# odd_v1.net
KiCad netlist of a schematic drawn in EAGLE
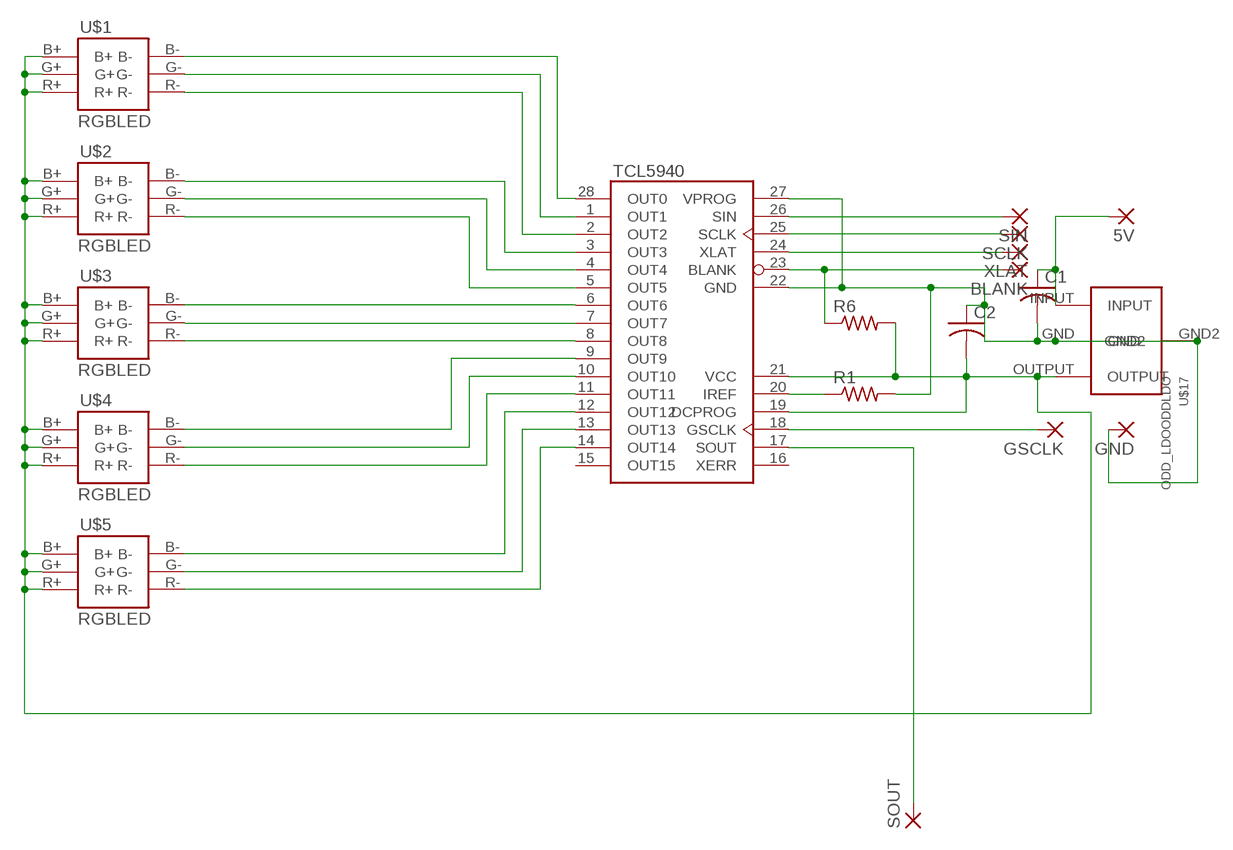
[diagram p0: schematic, sheet 1]

(export (version "E")
  (design (tool "Eeschema 10.0.6"))
  (components
    (comp (ref "5V")
      (value "2,54/1,1")
      (footprint "eagle-import:2,54_1,1")
      (libsource (lib "eagle-import") (part "2,54/1,1"))
    )
    (comp (ref "BLANK")
      (value "2,54/1,1")
      (footprint "eagle-import:2,54_1,1")
      (libsource (lib "eagle-import") (part "2,54/1,1"))
    )
    (comp (ref "C1")
      (value "C-US075-032X103")
      (footprint "eagle-import:C075-032X103")
      (libsource (lib "eagle-import") (part "C-US075-032X103"))
    )
    (comp (ref "C2")
      (value "C-US075-032X103")
      (footprint "eagle-import:C075-032X103")
      (libsource (lib "eagle-import") (part "C-US075-032X103"))
    )
    (comp (ref "GND")
      (value "2,54/1,1")
      (footprint "eagle-import:2,54_1,1")
      (libsource (lib "eagle-import") (part "2,54/1,1"))
    )
    (comp (ref "GSCLK")
      (value "2,54/1,1")
      (footprint "eagle-import:2,54_1,1")
      (libsource (lib "eagle-import") (part "2,54/1,1"))
    )
    (comp (ref "IC1")
      (value "TCL5940")
      (footprint "eagle-import:DIP28")
      (libsource (lib "eagle-import") (part "TCL5940"))
    )
    (comp (ref "R1")
      (value "R-US_0204/7")
      (footprint "eagle-import:0204_7")
      (libsource (lib "eagle-import") (part "R-US_0204/7"))
    )
    (comp (ref "R6")
      (value "R-US_0204/7")
      (footprint "eagle-import:0204_7")
      (libsource (lib "eagle-import") (part "R-US_0204/7"))
    )
    (comp (ref "SCLK")
      (value "2,54/1,1")
      (footprint "eagle-import:2,54_1,1")
      (libsource (lib "eagle-import") (part "2,54/1,1"))
    )
    (comp (ref "SIN")
      (value "2,54/1,1")
      (footprint "eagle-import:2,54_1,1")
      (libsource (lib "eagle-import") (part "2,54/1,1"))
    )
    (comp (ref "SOUT")
      (value "2,54/1,1")
      (footprint "eagle-import:2,54_1,1")
      (libsource (lib "eagle-import") (part "2,54/1,1"))
    )
    (comp (ref "U$1")
      (value "RGBLED")
      (footprint "eagle-import:6PADSMD")
      (libsource (lib "eagle-import") (part "CREESMDRGBLED6PADSMD"))
    )
    (comp (ref "U$2")
      (value "RGBLED")
      (footprint "eagle-import:6PADSMD")
      (libsource (lib "eagle-import") (part "CREESMDRGBLED6PADSMD"))
    )
    (comp (ref "U$3")
      (value "RGBLED")
      (footprint "eagle-import:6PADSMD")
      (libsource (lib "eagle-import") (part "CREESMDRGBLED6PADSMD"))
    )
    (comp (ref "U$4")
      (value "RGBLED")
      (footprint "eagle-import:6PADSMD")
      (libsource (lib "eagle-import") (part "CREESMDRGBLED6PADSMD"))
    )
    (comp (ref "U$5")
      (value "RGBLED")
      (footprint "eagle-import:6PADSMD")
      (libsource (lib "eagle-import") (part "CREESMDRGBLED6PADSMD"))
    )
    (comp (ref "U$17")
      (value "ODD_LDOODDLDO")
      (footprint "eagle-import:4PINLDO")
      (libsource (lib "eagle-import") (part "ODD_LDOODDLDO"))
    )
    (comp (ref "XLAT")
      (value "2,54/1,1")
      (footprint "eagle-import:2,54_1,1")
      (libsource (lib "eagle-import") (part "2,54/1,1"))
    )
  )
  (nets
    (net (code "1") (name "Net-(5V-P)") (class "Default")
      (node (ref "5V") (pin "1") (pinfunction "P_1") (pintype "passive"))
      (node (ref "C1") (pin "1") (pinfunction "1_1") (pintype "passive"))
      (node (ref "U$17") (pin "INPUT") (pinfunction "INPUT_INPUT") (pintype "bidirectional"))
    )
    (net (code "2") (name "Net-(BLANK-P)") (class "Default")
      (node (ref "BLANK") (pin "1") (pinfunction "P_1") (pintype "passive"))
      (node (ref "IC1") (pin "23") (pinfunction "BLANK_23") (pintype "input"))
      (node (ref "R6") (pin "1") (pinfunction "1_1") (pintype "passive"))
    )
    (net (code "3") (name "Net-(GND-P)") (class "Default")
      (node (ref "C1") (pin "2") (pinfunction "2_2") (pintype "passive"))
      (node (ref "C2") (pin "1") (pinfunction "1_1") (pintype "passive"))
      (node (ref "GND") (pin "1") (pinfunction "P_1") (pintype "passive"))
      (node (ref "IC1") (pin "22") (pinfunction "GND_22") (pintype "power_in"))
      (node (ref "IC1") (pin "27") (pinfunction "VPROG_27") (pintype "bidirectional"))
      (node (ref "R1") (pin "2") (pinfunction "2_2") (pintype "passive"))
      (node (ref "U$17") (pin "GND") (pinfunction "GND_GND") (pintype "bidirectional"))
      (node (ref "U$17") (pin "GND2") (pinfunction "GND2_GND2") (pintype "bidirectional"))
    )
    (net (code "4") (name "Net-(GSCLK-P)") (class "Default")
      (node (ref "GSCLK") (pin "1") (pinfunction "P_1") (pintype "passive"))
      (node (ref "IC1") (pin "18") (pinfunction "GSCLK_18") (pintype "input"))
    )
    (net (code "5") (name "Net-(IC1-DCPROG)") (class "Default")
      (node (ref "C2") (pin "2") (pinfunction "2_2") (pintype "passive"))
      (node (ref "IC1") (pin "19") (pinfunction "DCPROG_19") (pintype "input"))
      (node (ref "IC1") (pin "21") (pinfunction "VCC_21") (pintype "power_in"))
      (node (ref "R6") (pin "2") (pinfunction "2_2") (pintype "passive"))
      (node (ref "U$1") (pin "B+") (pinfunction "B+_B+") (pintype "bidirectional"))
      (node (ref "U$1") (pin "G+") (pinfunction "G+_G+") (pintype "bidirectional"))
      (node (ref "U$1") (pin "R+") (pinfunction "R+_R+") (pintype "bidirectional"))
      (node (ref "U$17") (pin "OUTPUT") (pinfunction "OUTPUT_OUTPUT") (pintype "bidirectional"))
      (node (ref "U$2") (pin "B+") (pinfunction "B+_B+") (pintype "bidirectional"))
      (node (ref "U$2") (pin "G+") (pinfunction "G+_G+") (pintype "bidirectional"))
      (node (ref "U$2") (pin "R+") (pinfunction "R+_R+") (pintype "bidirectional"))
      (node (ref "U$3") (pin "B+") (pinfunction "B+_B+") (pintype "bidirectional"))
      (node (ref "U$3") (pin "G+") (pinfunction "G+_G+") (pintype "bidirectional"))
      (node (ref "U$3") (pin "R+") (pinfunction "R+_R+") (pintype "bidirectional"))
      (node (ref "U$4") (pin "B+") (pinfunction "B+_B+") (pintype "bidirectional"))
      (node (ref "U$4") (pin "G+") (pinfunction "G+_G+") (pintype "bidirectional"))
      (node (ref "U$4") (pin "R+") (pinfunction "R+_R+") (pintype "bidirectional"))
      (node (ref "U$5") (pin "B+") (pinfunction "B+_B+") (pintype "bidirectional"))
      (node (ref "U$5") (pin "G+") (pinfunction "G+_G+") (pintype "bidirectional"))
      (node (ref "U$5") (pin "R+") (pinfunction "R+_R+") (pintype "bidirectional"))
    )
    (net (code "6") (name "Net-(IC1-IREF)") (class "Default")
      (node (ref "IC1") (pin "20") (pinfunction "IREF_20") (pintype "input"))
      (node (ref "R1") (pin "1") (pinfunction "1_1") (pintype "passive"))
    )
    (net (code "7") (name "Net-(IC1-OUT0)") (class "Default")
      (node (ref "IC1") (pin "28") (pinfunction "OUT0_28") (pintype "output"))
      (node (ref "U$1") (pin "B-") (pinfunction "B-_B-") (pintype "bidirectional"))
    )
    (net (code "8") (name "Net-(IC1-OUT1)") (class "Default")
      (node (ref "IC1") (pin "1") (pinfunction "OUT1_1") (pintype "output"))
      (node (ref "U$1") (pin "G-") (pinfunction "G-_G-") (pintype "bidirectional"))
    )
    (net (code "9") (name "Net-(IC1-OUT2)") (class "Default")
      (node (ref "IC1") (pin "2") (pinfunction "OUT2_2") (pintype "output"))
      (node (ref "U$1") (pin "R-") (pinfunction "R-_R-") (pintype "bidirectional"))
    )
    (net (code "10") (name "Net-(IC1-OUT3)") (class "Default")
      (node (ref "IC1") (pin "3") (pinfunction "OUT3_3") (pintype "output"))
      (node (ref "U$2") (pin "B-") (pinfunction "B-_B-") (pintype "bidirectional"))
    )
    (net (code "11") (name "Net-(IC1-OUT4)") (class "Default")
      (node (ref "IC1") (pin "4") (pinfunction "OUT4_4") (pintype "output"))
      (node (ref "U$2") (pin "G-") (pinfunction "G-_G-") (pintype "bidirectional"))
    )
    (net (code "12") (name "Net-(IC1-OUT5)") (class "Default")
      (node (ref "IC1") (pin "5") (pinfunction "OUT5_5") (pintype "output"))
      (node (ref "U$2") (pin "R-") (pinfunction "R-_R-") (pintype "bidirectional"))
    )
    (net (code "13") (name "Net-(IC1-OUT6)") (class "Default")
      (node (ref "IC1") (pin "6") (pinfunction "OUT6_6") (pintype "output"))
      (node (ref "U$3") (pin "B-") (pinfunction "B-_B-") (pintype "bidirectional"))
    )
    (net (code "14") (name "Net-(IC1-OUT7)") (class "Default")
      (node (ref "IC1") (pin "7") (pinfunction "OUT7_7") (pintype "output"))
      (node (ref "U$3") (pin "G-") (pinfunction "G-_G-") (pintype "bidirectional"))
    )
    (net (code "15") (name "Net-(IC1-OUT8)") (class "Default")
      (node (ref "IC1") (pin "8") (pinfunction "OUT8_8") (pintype "output"))
      (node (ref "U$3") (pin "R-") (pinfunction "R-_R-") (pintype "bidirectional"))
    )
    (net (code "16") (name "Net-(IC1-OUT9)") (class "Default")
      (node (ref "IC1") (pin "9") (pinfunction "OUT9_9") (pintype "output"))
      (node (ref "U$4") (pin "B-") (pinfunction "B-_B-") (pintype "bidirectional"))
    )
    (net (code "17") (name "Net-(IC1-OUT10)") (class "Default")
      (node (ref "IC1") (pin "10") (pinfunction "OUT10_10") (pintype "output"))
      (node (ref "U$4") (pin "G-") (pinfunction "G-_G-") (pintype "bidirectional"))
    )
    (net (code "18") (name "Net-(IC1-OUT11)") (class "Default")
      (node (ref "IC1") (pin "11") (pinfunction "OUT11_11") (pintype "output"))
      (node (ref "U$4") (pin "R-") (pinfunction "R-_R-") (pintype "bidirectional"))
    )
    (net (code "19") (name "Net-(IC1-OUT12)") (class "Default")
      (node (ref "IC1") (pin "12") (pinfunction "OUT12_12") (pintype "output"))
      (node (ref "U$5") (pin "B-") (pinfunction "B-_B-") (pintype "bidirectional"))
    )
    (net (code "20") (name "Net-(IC1-OUT13)") (class "Default")
      (node (ref "IC1") (pin "13") (pinfunction "OUT13_13") (pintype "output"))
      (node (ref "U$5") (pin "G-") (pinfunction "G-_G-") (pintype "bidirectional"))
    )
    (net (code "21") (name "Net-(IC1-OUT14)") (class "Default")
      (node (ref "IC1") (pin "14") (pinfunction "OUT14_14") (pintype "output"))
      (node (ref "U$5") (pin "R-") (pinfunction "R-_R-") (pintype "bidirectional"))
    )
    (net (code "22") (name "Net-(IC1-SCLK)") (class "Default")
      (node (ref "IC1") (pin "25") (pinfunction "SCLK_25") (pintype "input"))
      (node (ref "SCLK") (pin "1") (pinfunction "P_1") (pintype "passive"))
    )
    (net (code "23") (name "Net-(IC1-SIN)") (class "Default")
      (node (ref "IC1") (pin "26") (pinfunction "SIN_26") (pintype "input"))
      (node (ref "SIN") (pin "1") (pinfunction "P_1") (pintype "passive"))
    )
    (net (code "24") (name "Net-(IC1-SOUT)") (class "Default")
      (node (ref "IC1") (pin "17") (pinfunction "SOUT_17") (pintype "output"))
      (node (ref "SOUT") (pin "1") (pinfunction "P_1") (pintype "passive"))
    )
    (net (code "25") (name "Net-(IC1-XLAT)") (class "Default")
      (node (ref "IC1") (pin "24") (pinfunction "XLAT_24") (pintype "input"))
      (node (ref "XLAT") (pin "1") (pinfunction "P_1") (pintype "passive"))
    )
    (net (code "26") (name "unconnected-(IC1-OUT15-Pad15)") (class "Default")
      (node (ref "IC1") (pin "15") (pinfunction "OUT15_15") (pintype "output"))
    )
    (net (code "27") (name "unconnected-(IC1-XERR-Pad16)") (class "Default")
      (node (ref "IC1") (pin "16") (pinfunction "XERR_16") (pintype "output"))
    )
  )
)
